# BCR_Unit.net
KiCad netlist of a schematic drawn in Altium Designer
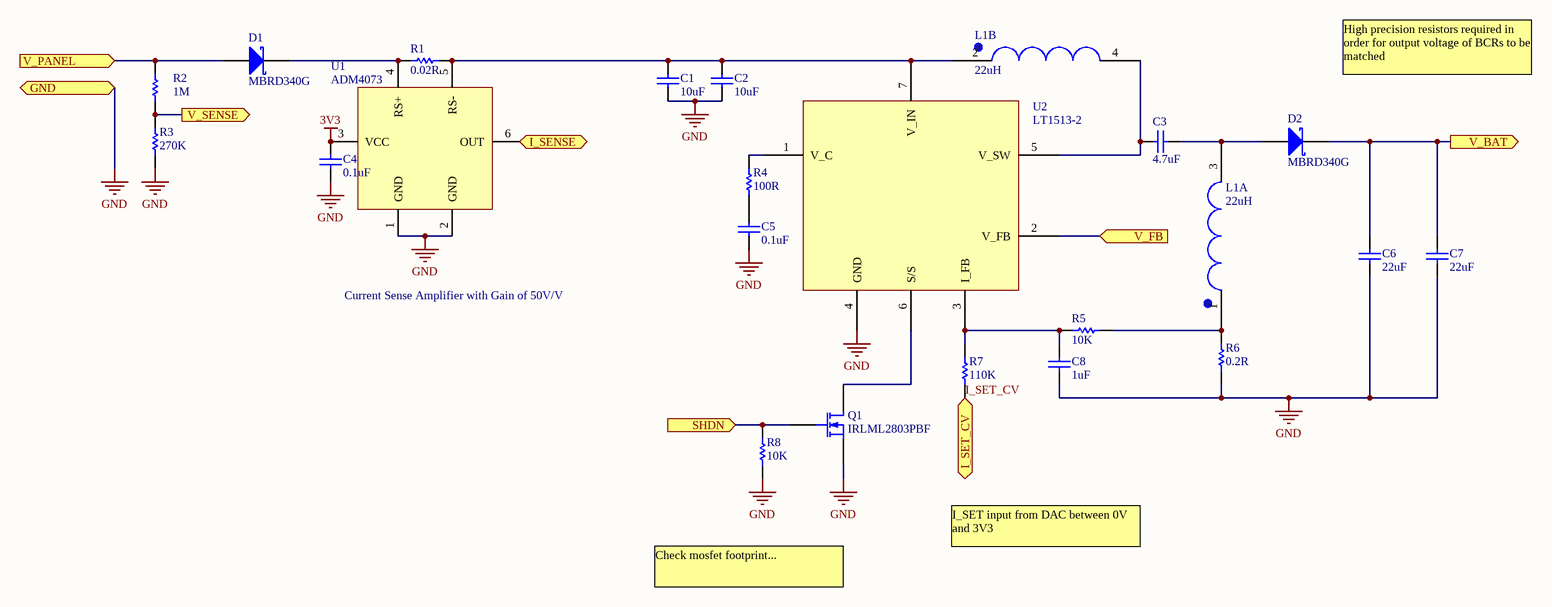
[diagram p0: BCR_Unit.SchDoc]

(export (version "E")
  (design (tool "Eeschema 10.0.6"))
  (components
    (comp (ref "C1")
      (value "10uF")
      (footprint "CAPC3225M")
      (description "Capacitor")
      (fields (field (name "Comment") "Cap") (field (name "PUBLISHER") "Altium Limited"))
      (libsource (lib "Miscellaneous Devices") (part "Cap"))
    )
    (comp (ref "C2")
      (value "10uF")
      (footprint "CAPC3225M")
      (description "Capacitor")
      (fields (field (name "Comment") "Cap") (field (name "PUBLISHER") "Altium Limited"))
      (libsource (lib "Miscellaneous Devices") (part "Cap"))
    )
    (comp (ref "C3")
      (value "4.7uF")
      (footprint "CAPC3225M")
      (description "Capacitor")
      (fields (field (name "Comment") "Cap") (field (name "PUBLISHER") "Altium Limited"))
      (libsource (lib "Miscellaneous Devices") (part "Cap"))
    )
    (comp (ref "C4")
      (value "0.1uF")
      (footprint "CAPC2012M")
      (description "Capacitor")
      (fields (field (name "Comment") "Cap") (field (name "PUBLISHER") "Altium Limited"))
      (libsource (lib "Miscellaneous Devices") (part "Cap"))
    )
    (comp (ref "C5")
      (value "0.1uF")
      (footprint "CAPC2012M")
      (description "Capacitor")
      (fields (field (name "Comment") "Cap") (field (name "PUBLISHER") "Altium Limited"))
      (libsource (lib "Miscellaneous Devices") (part "Cap"))
    )
    (comp (ref "C6")
      (value "22uF")
      (footprint "CAPC4532M")
      (description "Capacitor")
      (fields (field (name "Comment") "Cap") (field (name "PUBLISHER") "Altium Limited"))
      (libsource (lib "Miscellaneous Devices") (part "Cap"))
    )
    (comp (ref "C7")
      (value "22uF")
      (footprint "CAPC4532M")
      (description "Capacitor")
      (fields (field (name "Comment") "Cap") (field (name "PUBLISHER") "Altium Limited"))
      (libsource (lib "Miscellaneous Devices") (part "Cap"))
    )
    (comp (ref "C8")
      (value "1uF")
      (footprint "CAPC2012M")
      (description "Capacitor")
      (fields (field (name "Comment") "Cap") (field (name "PUBLISHER") "Altium Limited"))
      (libsource (lib "Miscellaneous Devices") (part "Cap"))
    )
    (comp (ref "D1")
      (value "MBRD340G")
      (footprint "TO229P990X238-3N")
      (description "Schottky Rectifier")
      (fields (field (name "PUBLISHER") "Altium Limited"))
      (libsource (lib "Miscellaneous Devices") (part "Diode 11DQ03"))
    )
    (comp (ref "D2")
      (value "MBRD340G")
      (footprint "TO229P990X238-3N")
      (description "Schottky Rectifier")
      (fields (field (name "PUBLISHER") "Altium Limited"))
      (libsource (lib "Miscellaneous Devices") (part "Diode 11DQ03"))
    )
    (comp (ref "L1")
      (value "22uH")
      (footprint "DRQ125")
      (fields (field (name "Comment") "DRQ125 Dual Inductor"))
      (libsource (lib "LT1513") (part "DRQ125 Dual Inductor"))
    )
    (comp (ref "Q1")
      (value "IRLML2803PBF")
      (footprint "SOT-23_N")
      (description "N-Channel MOSFET")
      (fields (field (name "PUBLISHER") "Altium Limited"))
      (libsource (lib "Miscellaneous Devices") (part "MOSFET-N"))
    )
    (comp (ref "R1")
      (value "0.02R")
      (footprint "RESC2012M")
      (description "Resistor")
      (fields (field (name "Comment") "Res1") (field (name "PUBLISHER") "Altium Limited"))
      (libsource (lib "Miscellaneous Devices") (part "Res1"))
    )
    (comp (ref "R2")
      (value "1M")
      (footprint "RESC2012M")
      (description "Resistor")
      (fields (field (name "Comment") "Res1") (field (name "PUBLISHER") "Altium Limited"))
      (libsource (lib "Miscellaneous Devices") (part "Res1"))
    )
    (comp (ref "R3")
      (value "270K")
      (footprint "RESC2012M")
      (description "Resistor")
      (fields (field (name "Comment") "Res1") (field (name "PUBLISHER") "Altium Limited"))
      (libsource (lib "Miscellaneous Devices") (part "Res1"))
    )
    (comp (ref "R4")
      (value "100R")
      (footprint "RESC2012M")
      (description "Resistor")
      (fields (field (name "Comment") "Res1") (field (name "PUBLISHER") "Altium Limited"))
      (libsource (lib "Miscellaneous Devices") (part "Res1"))
    )
    (comp (ref "R5")
      (value "10K")
      (footprint "RESC2012M")
      (description "Resistor")
      (fields (field (name "Comment") "Res1") (field (name "PUBLISHER") "Altium Limited"))
      (libsource (lib "Miscellaneous Devices") (part "Res1"))
    )
    (comp (ref "R6")
      (value "0.2R")
      (footprint "RESC2012M")
      (description "Resistor")
      (fields (field (name "Comment") "Res1") (field (name "PUBLISHER") "Altium Limited"))
      (libsource (lib "Miscellaneous Devices") (part "Res1"))
    )
    (comp (ref "R7")
      (value "110K")
      (footprint "RESC2012M")
      (description "Resistor")
      (fields (field (name "Comment") "Res1") (field (name "PUBLISHER") "Altium Limited"))
      (libsource (lib "Miscellaneous Devices") (part "Res1"))
    )
    (comp (ref "R8")
      (value "10K")
      (footprint "RESC2012M")
      (description "Resistor")
      (fields (field (name "Comment") "Res1") (field (name "PUBLISHER") "Altium Limited"))
      (libsource (lib "Miscellaneous Devices") (part "Res1"))
    )
    (comp (ref "U1")
      (value "ADM4073")
      (footprint "SOT95P285X145-6N")
      (description "Current Sense Amplifer")
      (libsource (lib "Schlib1") (part "ADM4073"))
    )
    (comp (ref "U2")
      (value "LT1513-2")
      (footprint "TO152P1396X238-8N")
      (libsource (lib "LT1513") (part "LT1513"))
    )
  )
  (nets
    (net (code "1") (name "/I_SENSE") (class "Default")
      (node (ref "U1") (pin "6") (pinfunction "OUT_6") (pintype "passive"))
    )
    (net (code "2") (name "/I_SET_CV") (class "Default")
      (node (ref "R7") (pin "2") (pinfunction "2_2") (pintype "passive"))
    )
    (net (code "3") (name "/SHDN") (class "Default")
      (node (ref "Q1") (pin "2") (pinfunction "G_2") (pintype "passive"))
      (node (ref "R8") (pin "1") (pinfunction "1_1") (pintype "passive"))
    )
    (net (code "4") (name "/V_BAT") (class "Default")
      (node (ref "C6") (pin "1") (pinfunction "1_1") (pintype "passive"))
      (node (ref "C7") (pin "1") (pinfunction "1_1") (pintype "passive"))
      (node (ref "D2") (pin "2") (pinfunction "K_2") (pintype "passive"))
    )
    (net (code "5") (name "/V_FB") (class "Default")
      (node (ref "U2") (pin "2") (pinfunction "V_FB_2") (pintype "passive"))
    )
    (net (code "6") (name "/V_PANEL") (class "Default")
      (node (ref "D1") (pin "1") (pinfunction "A_1") (pintype "passive"))
      (node (ref "R2") (pin "1") (pinfunction "1_1") (pintype "passive"))
    )
    (net (code "7") (name "/V_SENSE") (class "Default")
      (node (ref "R2") (pin "2") (pinfunction "2_2") (pintype "passive"))
      (node (ref "R3") (pin "1") (pinfunction "1_1") (pintype "passive"))
    )
    (net (code "8") (name "3V3") (class "Default")
      (node (ref "C4") (pin "1") (pinfunction "1_1") (pintype "passive"))
      (node (ref "U1") (pin "3") (pinfunction "VCC_3") (pintype "passive"))
    )
    (net (code "9") (name "GND") (class "Default")
      (node (ref "C1") (pin "2") (pinfunction "2_2") (pintype "passive"))
      (node (ref "C2") (pin "2") (pinfunction "2_2") (pintype "passive"))
      (node (ref "C4") (pin "2") (pinfunction "2_2") (pintype "passive"))
      (node (ref "C5") (pin "2") (pinfunction "2_2") (pintype "passive"))
      (node (ref "C6") (pin "2") (pinfunction "2_2") (pintype "passive"))
      (node (ref "C7") (pin "2") (pinfunction "2_2") (pintype "passive"))
      (node (ref "C8") (pin "1") (pinfunction "1_1") (pintype "passive"))
      (node (ref "Q1") (pin "3") (pinfunction "S_3") (pintype "passive"))
      (node (ref "R3") (pin "2") (pinfunction "2_2") (pintype "passive"))
      (node (ref "R6") (pin "1") (pinfunction "1_1") (pintype "passive"))
      (node (ref "R8") (pin "2") (pinfunction "2_2") (pintype "passive"))
      (node (ref "U1") (pin "1") (pinfunction "GND_1") (pintype "passive"))
      (node (ref "U1") (pin "2") (pinfunction "GND_2") (pintype "passive"))
      (node (ref "U2") (pin "4") (pinfunction "GND_4") (pintype "passive"))
    )
    (net (code "10") (name "Net-(C5-Pad1)") (class "Default")
      (node (ref "C5") (pin "1") (pinfunction "1_1") (pintype "passive"))
      (node (ref "R4") (pin "2") (pinfunction "2_2") (pintype "passive"))
    )
    (net (code "11") (name "Net-(D1-K)") (class "Default")
      (node (ref "D1") (pin "2") (pinfunction "K_2") (pintype "passive"))
      (node (ref "R1") (pin "2") (pinfunction "2_2") (pintype "passive"))
      (node (ref "U1") (pin "4") (pinfunction "RS+_4") (pintype "passive"))
    )
    (net (code "12") (name "Net-(D2-A)") (class "Default")
      (node (ref "C3") (pin "1") (pinfunction "1_1") (pintype "passive"))
      (node (ref "D2") (pin "1") (pinfunction "A_1") (pintype "passive"))
      (node (ref "L1") (pin "3") (pinfunction "18_3") (pintype "passive"))
    )
    (net (code "13") (name "Net-(L1A-17)") (class "Default")
      (node (ref "L1") (pin "1") (pinfunction "17_1") (pintype "passive"))
      (node (ref "R5") (pin "1") (pinfunction "1_1") (pintype "passive"))
      (node (ref "R6") (pin "2") (pinfunction "2_2") (pintype "passive"))
    )
    (net (code "14") (name "Net-(L1B-17)") (class "Default")
      (node (ref "C1") (pin "1") (pinfunction "1_1") (pintype "passive"))
      (node (ref "C2") (pin "1") (pinfunction "1_1") (pintype "passive"))
      (node (ref "L1") (pin "2") (pinfunction "17_2") (pintype "passive"))
      (node (ref "R1") (pin "1") (pinfunction "1_1") (pintype "passive"))
      (node (ref "U1") (pin "5") (pinfunction "RS-_5") (pintype "passive"))
      (node (ref "U2") (pin "7") (pinfunction "V_IN_7") (pintype "passive"))
    )
    (net (code "15") (name "Net-(L1B-18)") (class "Default")
      (node (ref "C3") (pin "2") (pinfunction "2_2") (pintype "passive"))
      (node (ref "L1") (pin "4") (pinfunction "18_4") (pintype "passive"))
      (node (ref "U2") (pin "5") (pinfunction "V_SW_5") (pintype "passive"))
    )
    (net (code "16") (name "Net-(Q1-D)") (class "Default")
      (node (ref "Q1") (pin "1") (pinfunction "D_1") (pintype "passive"))
      (node (ref "U2") (pin "6") (pinfunction "S/S_6") (pintype "passive"))
    )
    (net (code "17") (name "Net-(U2-I_FB)") (class "Default")
      (node (ref "C8") (pin "2") (pinfunction "2_2") (pintype "passive"))
      (node (ref "R5") (pin "2") (pinfunction "2_2") (pintype "passive"))
      (node (ref "R7") (pin "1") (pinfunction "1_1") (pintype "passive"))
      (node (ref "U2") (pin "3") (pinfunction "I_FB_3") (pintype "passive"))
    )
    (net (code "18") (name "Net-(U2-V_C)") (class "Default")
      (node (ref "R4") (pin "1") (pinfunction "1_1") (pintype "passive"))
      (node (ref "U2") (pin "1") (pinfunction "V_C_1") (pintype "passive"))
    )
  )
)
